# 0_BlkDiag.net
KiCad netlist of a schematic drawn in Altium Designer
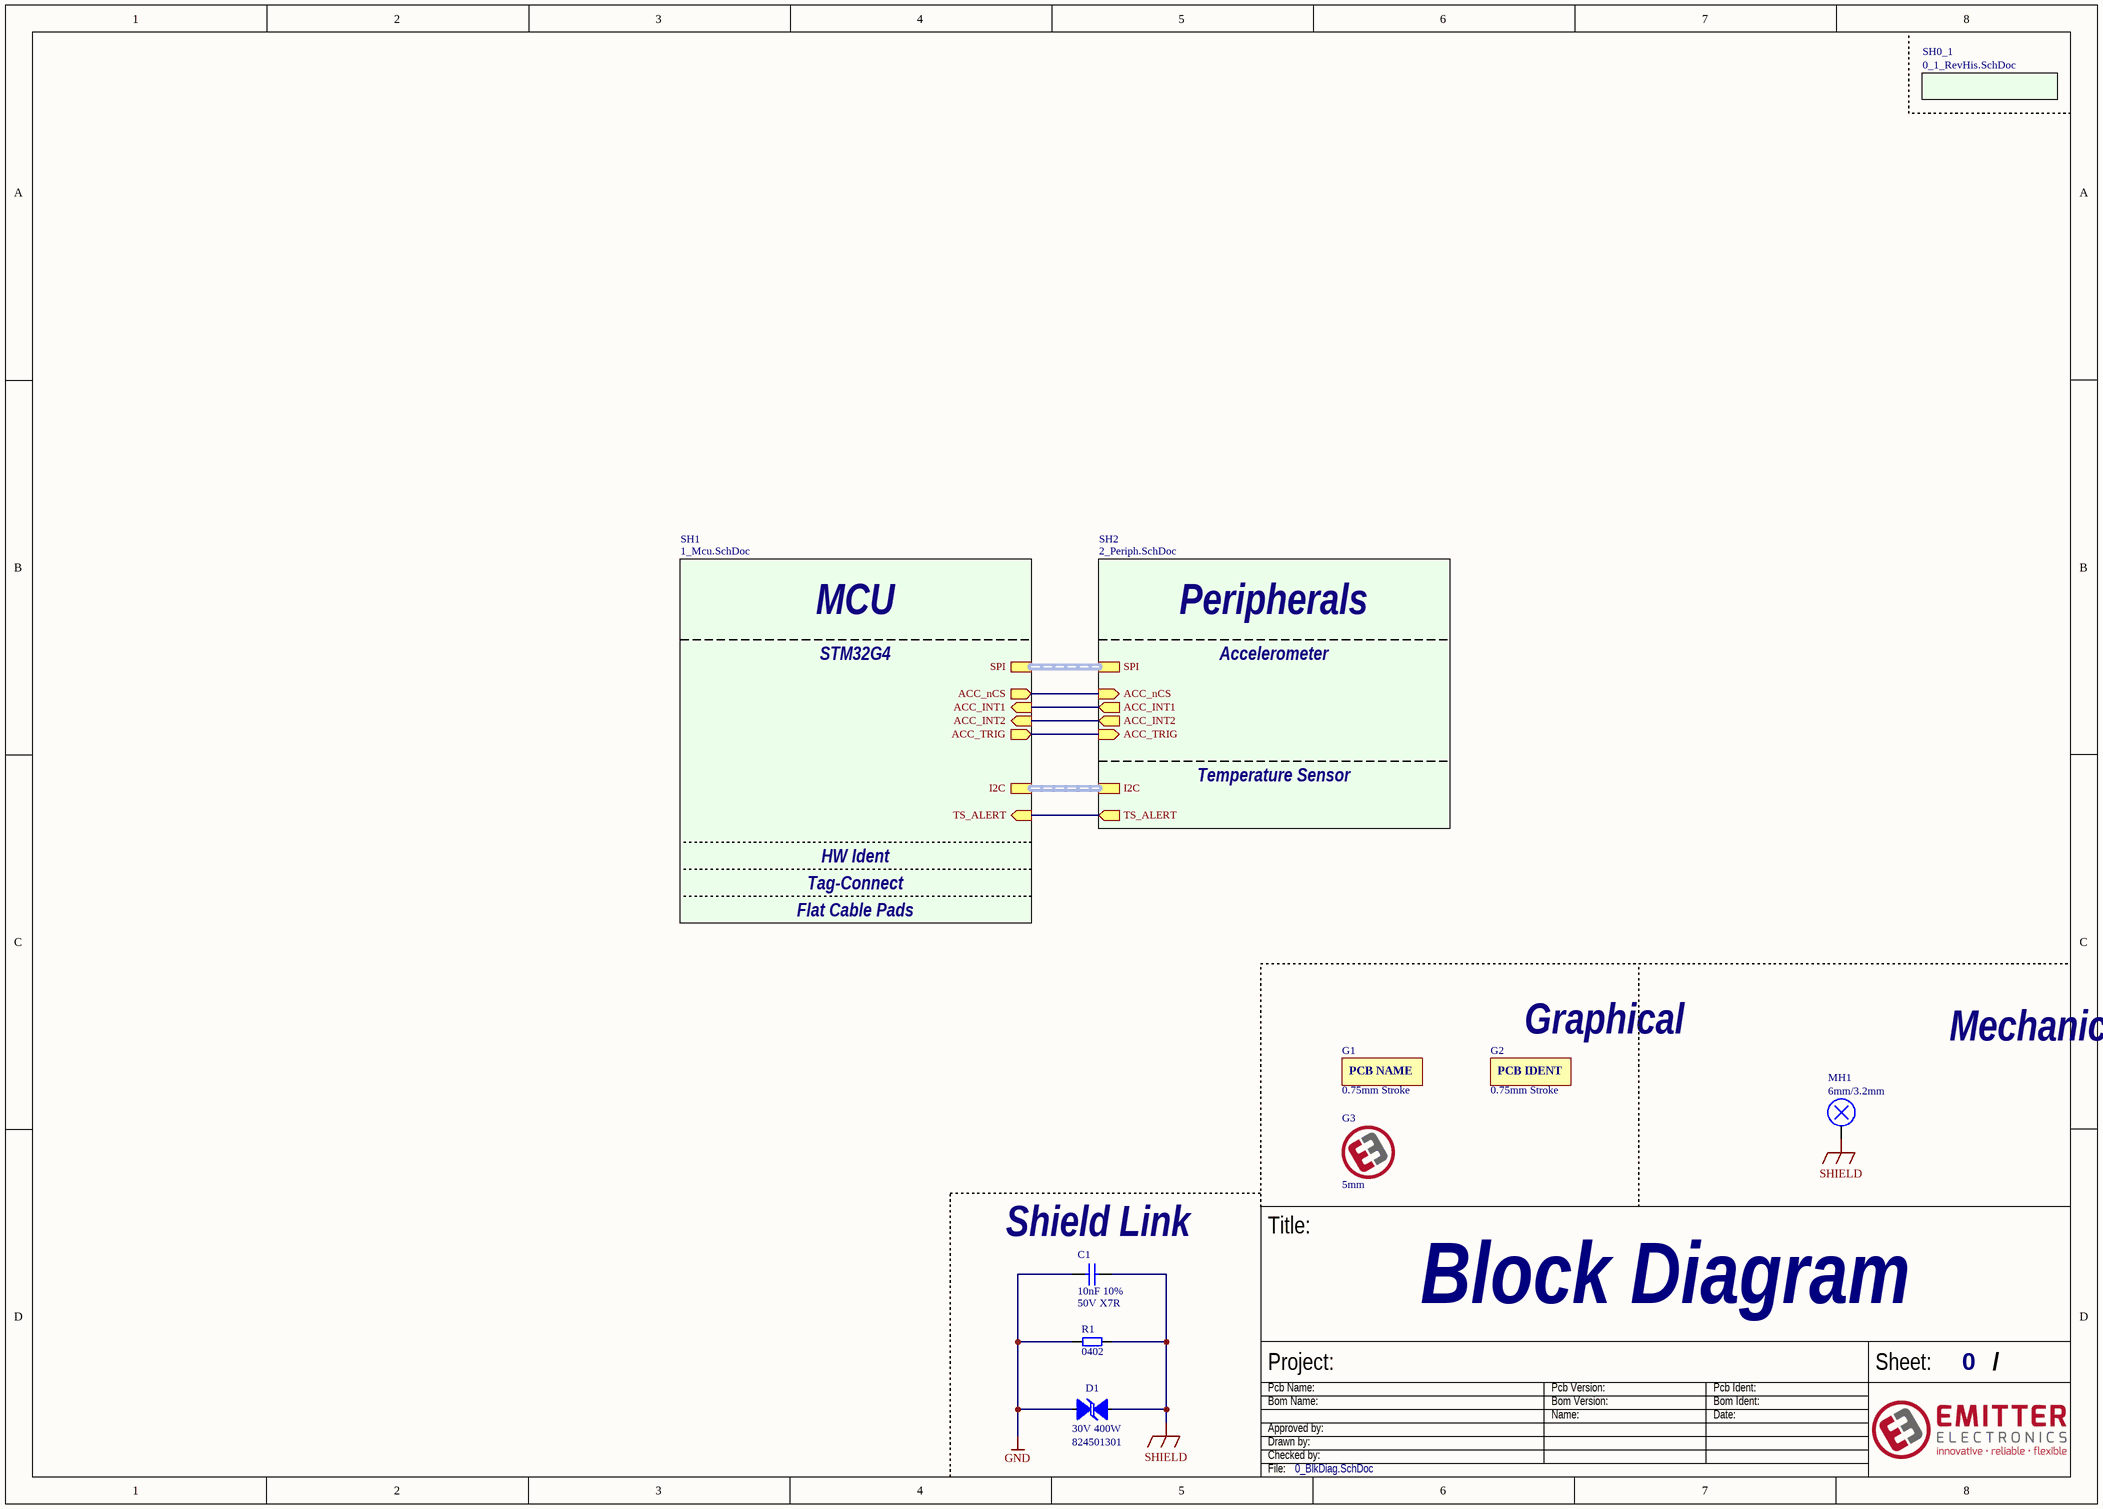
[diagram p0: 0_BlkDiag.SchDoc]

(export (version "E")
  (design (tool "Eeschema 10.0.6"))
  (components
    (comp (ref "C1")
      (value "CC0402KRX7R9BB103 ")
      (footprint "CAP_0402_L")
      (description "CAP 0402 10nF 10% 50V X7R")
      (fields
        (field (name "PARAM 1") "10nF 10%")
        (field (name "PARAM 2") "50V X7R")
        (field (name "AUTHOR") "GH")
      )
      (libsource (lib "AuralixAltiumLib") (part "CAP_0402_10nF_10%_50V_X7R_CC0402KRX7R9BB103"))
    )
    (comp (ref "D1")
      (value "824501301")
      (footprint "DIONM510X270_SMA_DO-214AC_L")
      (description "824501301 - TVS Diode, WE-TVSP Series, Bidirectional, 30 V, 48.4 V, DO-214AC, 2 Pins")
      (fields
        (field (name "MFR NO 1") "824501301")
        (field (name "PARAM 1") "30V 400W")
        (field (name "AUTHOR") "TV")
      )
      (libsource (lib "AuralixAltiumLib") (part "D-TVS-B_30V_400W_824501301"))
    )
    (comp (ref "G1")
      (value "/")
      (footprint "GRAPH_PCB_NAME_0.75MM_STROKE")
      (fields (field (name "PARAM 1") "0.75mm Stroke") (field (name "AUTHOR") "TV"))
      (libsource (lib "AuralixAltiumLib") (part "GRAPH_PCB_NAME_0.75MM_STROKE"))
    )
    (comp (ref "G2")
      (value "/")
      (footprint "GRAPH_PCB_IDENT_0.75MM_STROKE")
      (fields (field (name "PARAM 1") "0.75mm Stroke") (field (name "AUTHOR") "TV"))
      (libsource (lib "AuralixAltiumLib") (part "GRAPH_PCB_IDENT_0.75MM_STROKE"))
    )
    (comp (ref "G3")
      (value "/")
      (footprint "GRAPH_EMITTER_5MM")
      (fields (field (name "PARAM 1") "5mm") (field (name "AUTHOR") "JK"))
      (libsource (lib "AuralixAltiumLib") (part "GRAPH_EMITTER_5MM"))
    )
    (comp (ref "MH1")
      (value "/")
      (footprint "PS-MH_C600H320")
      (description "Mounting Hole - 6mm/3.2mm")
      (fields (field (name "PARAM 1") "6mm/3.2mm") (field (name "AUTHOR") "GH"))
      (libsource (lib "AuralixAltiumLib") (part "PS-MH_C600H320"))
    )
    (comp (ref "R1")
      (value "RES 0402")
      (footprint "RES_0402_L")
      (fields (field (name "PARAM 1") "0402") (field (name "AUTHOR") "TV"))
      (libsource (lib "AuralixAltiumLib") (part "RES_0402"))
    )
  )
  (nets
    (net (code "8") (name "GND") (class "Default")
      (node (ref "C1") (pin "1") (pinfunction "1_1") (pintype "passive"))
      (node (ref "D1") (pin "1") (pinfunction "1_1") (pintype "passive"))
      (node (ref "R1") (pin "1") (pinfunction "1_1") (pintype "passive"))
    )
    (net (code "9") (name "SHIELD") (class "Default")
      (node (ref "C1") (pin "2") (pinfunction "2_2") (pintype "passive"))
      (node (ref "D1") (pin "2") (pinfunction "2_2") (pintype "passive"))
      (node (ref "MH1") (pin "1") (pinfunction "1_1") (pintype "power_in"))
      (node (ref "R1") (pin "2") (pinfunction "2_2") (pintype "passive"))
    )
  )
)
